# led_cube.net
KiCad netlist of a schematic drawn in EAGLE
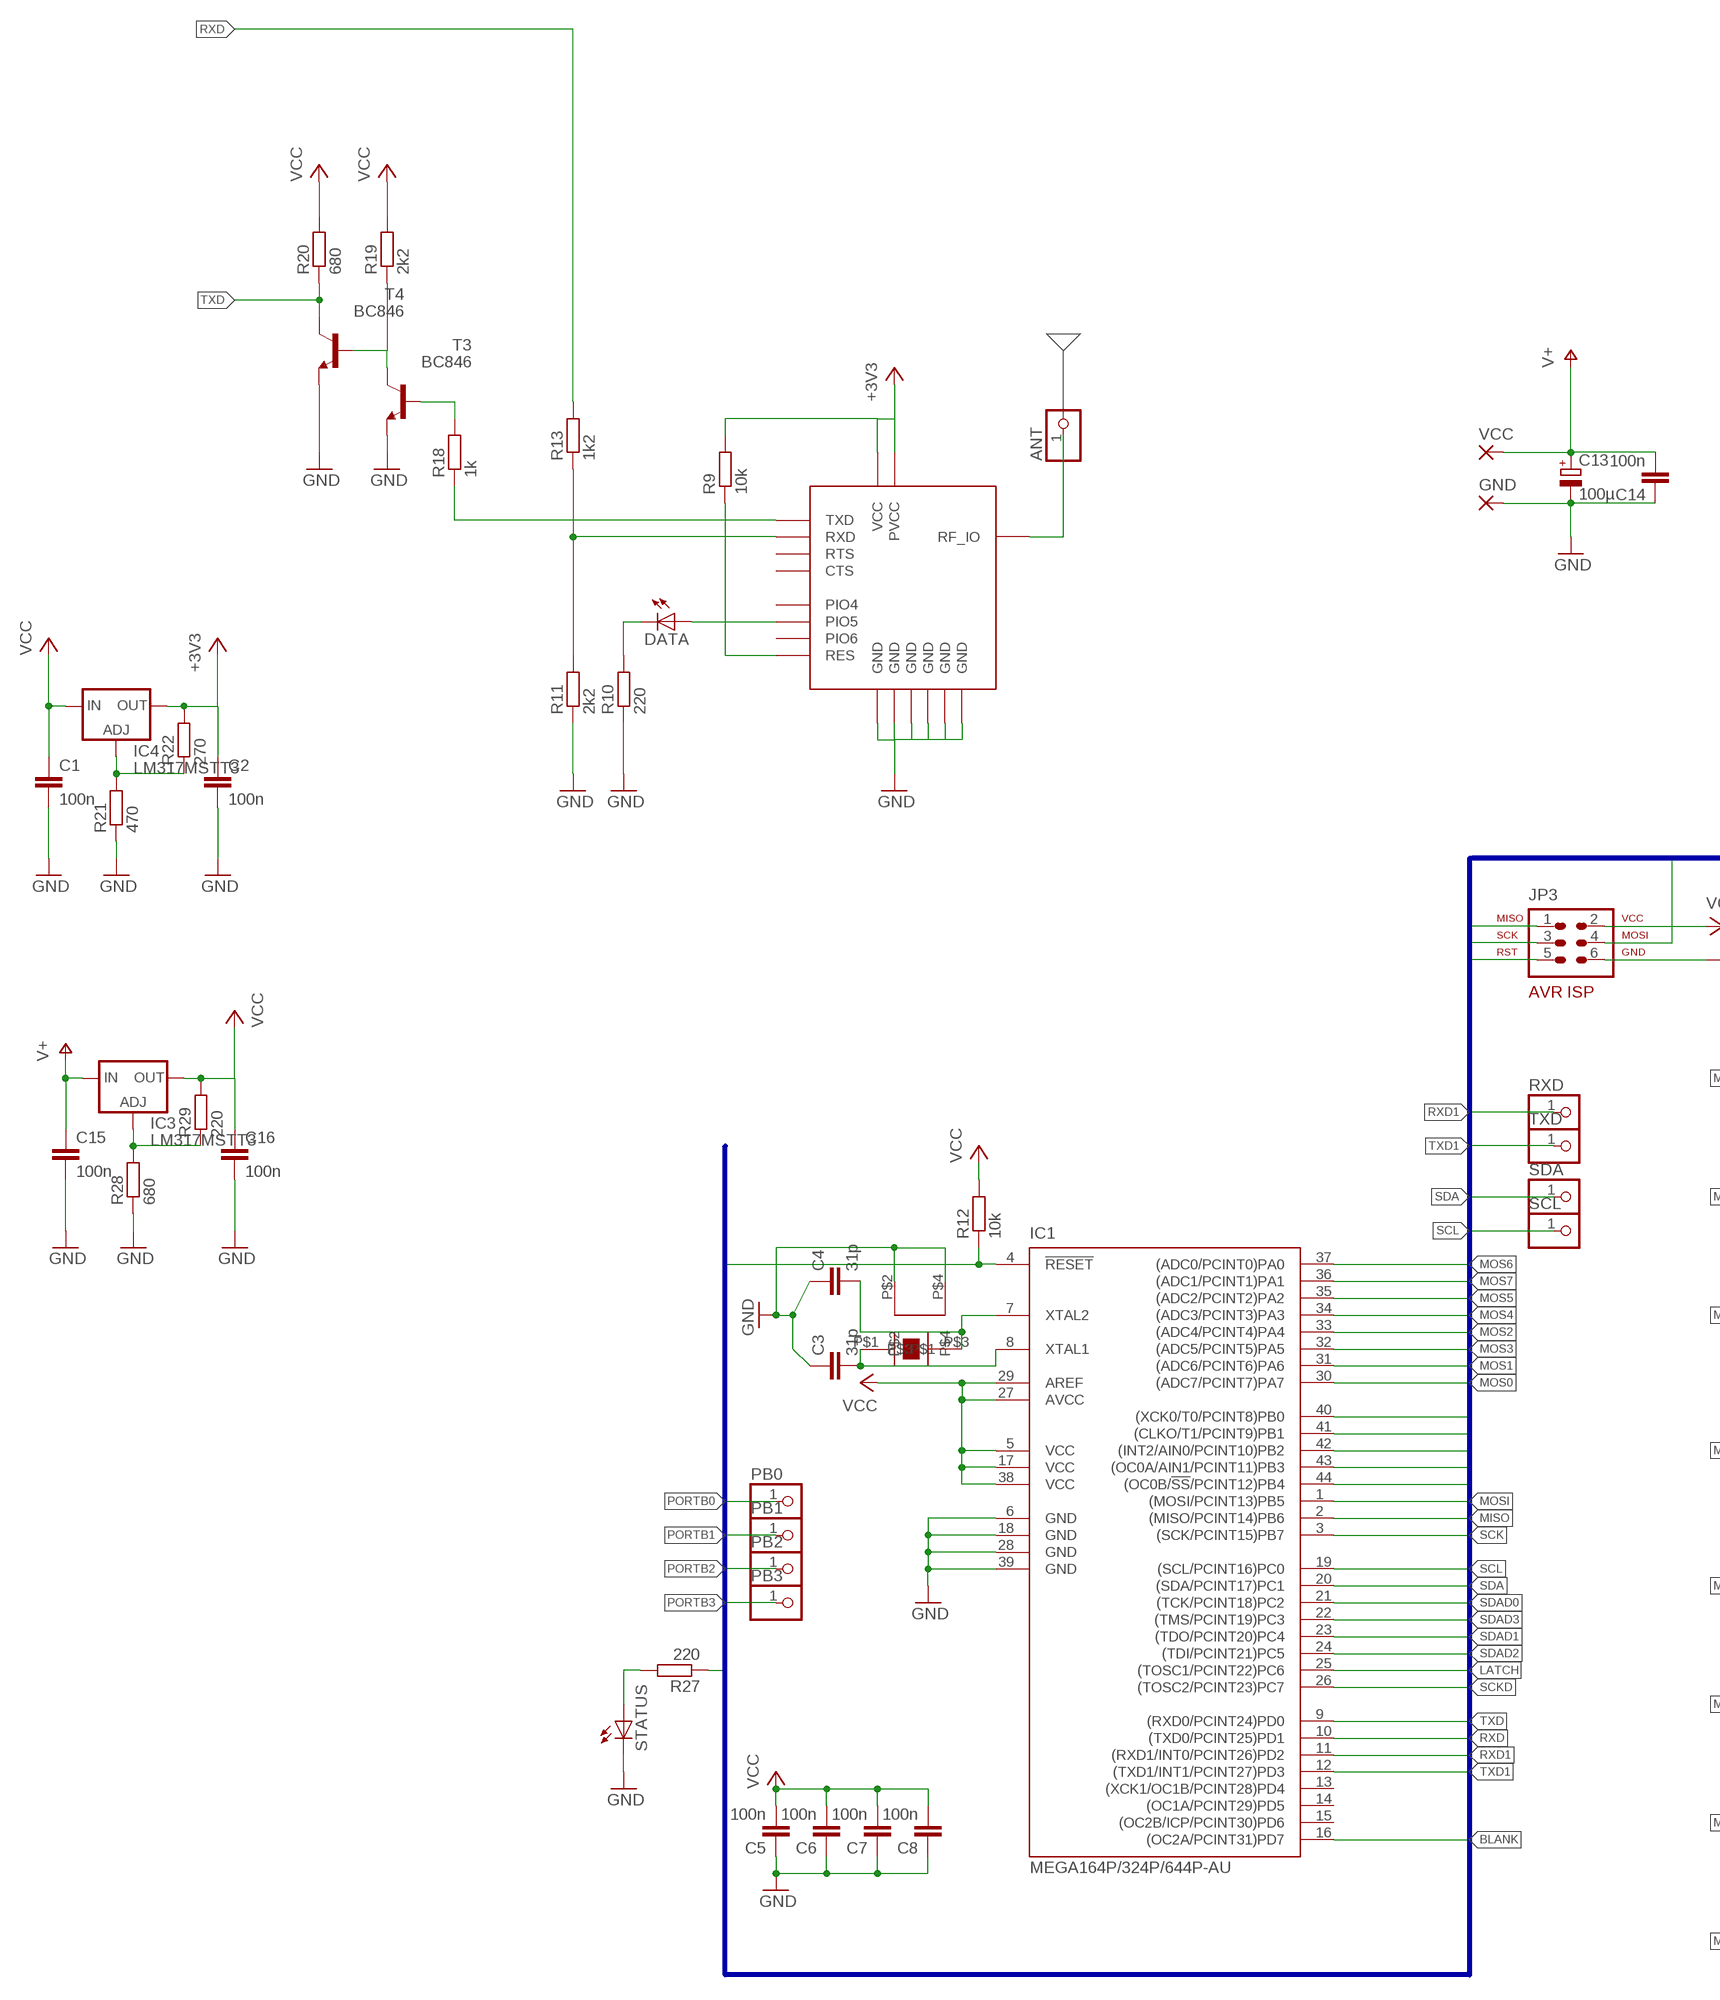
[diagram p0: schematic, sheet 1, part 1 of 2]
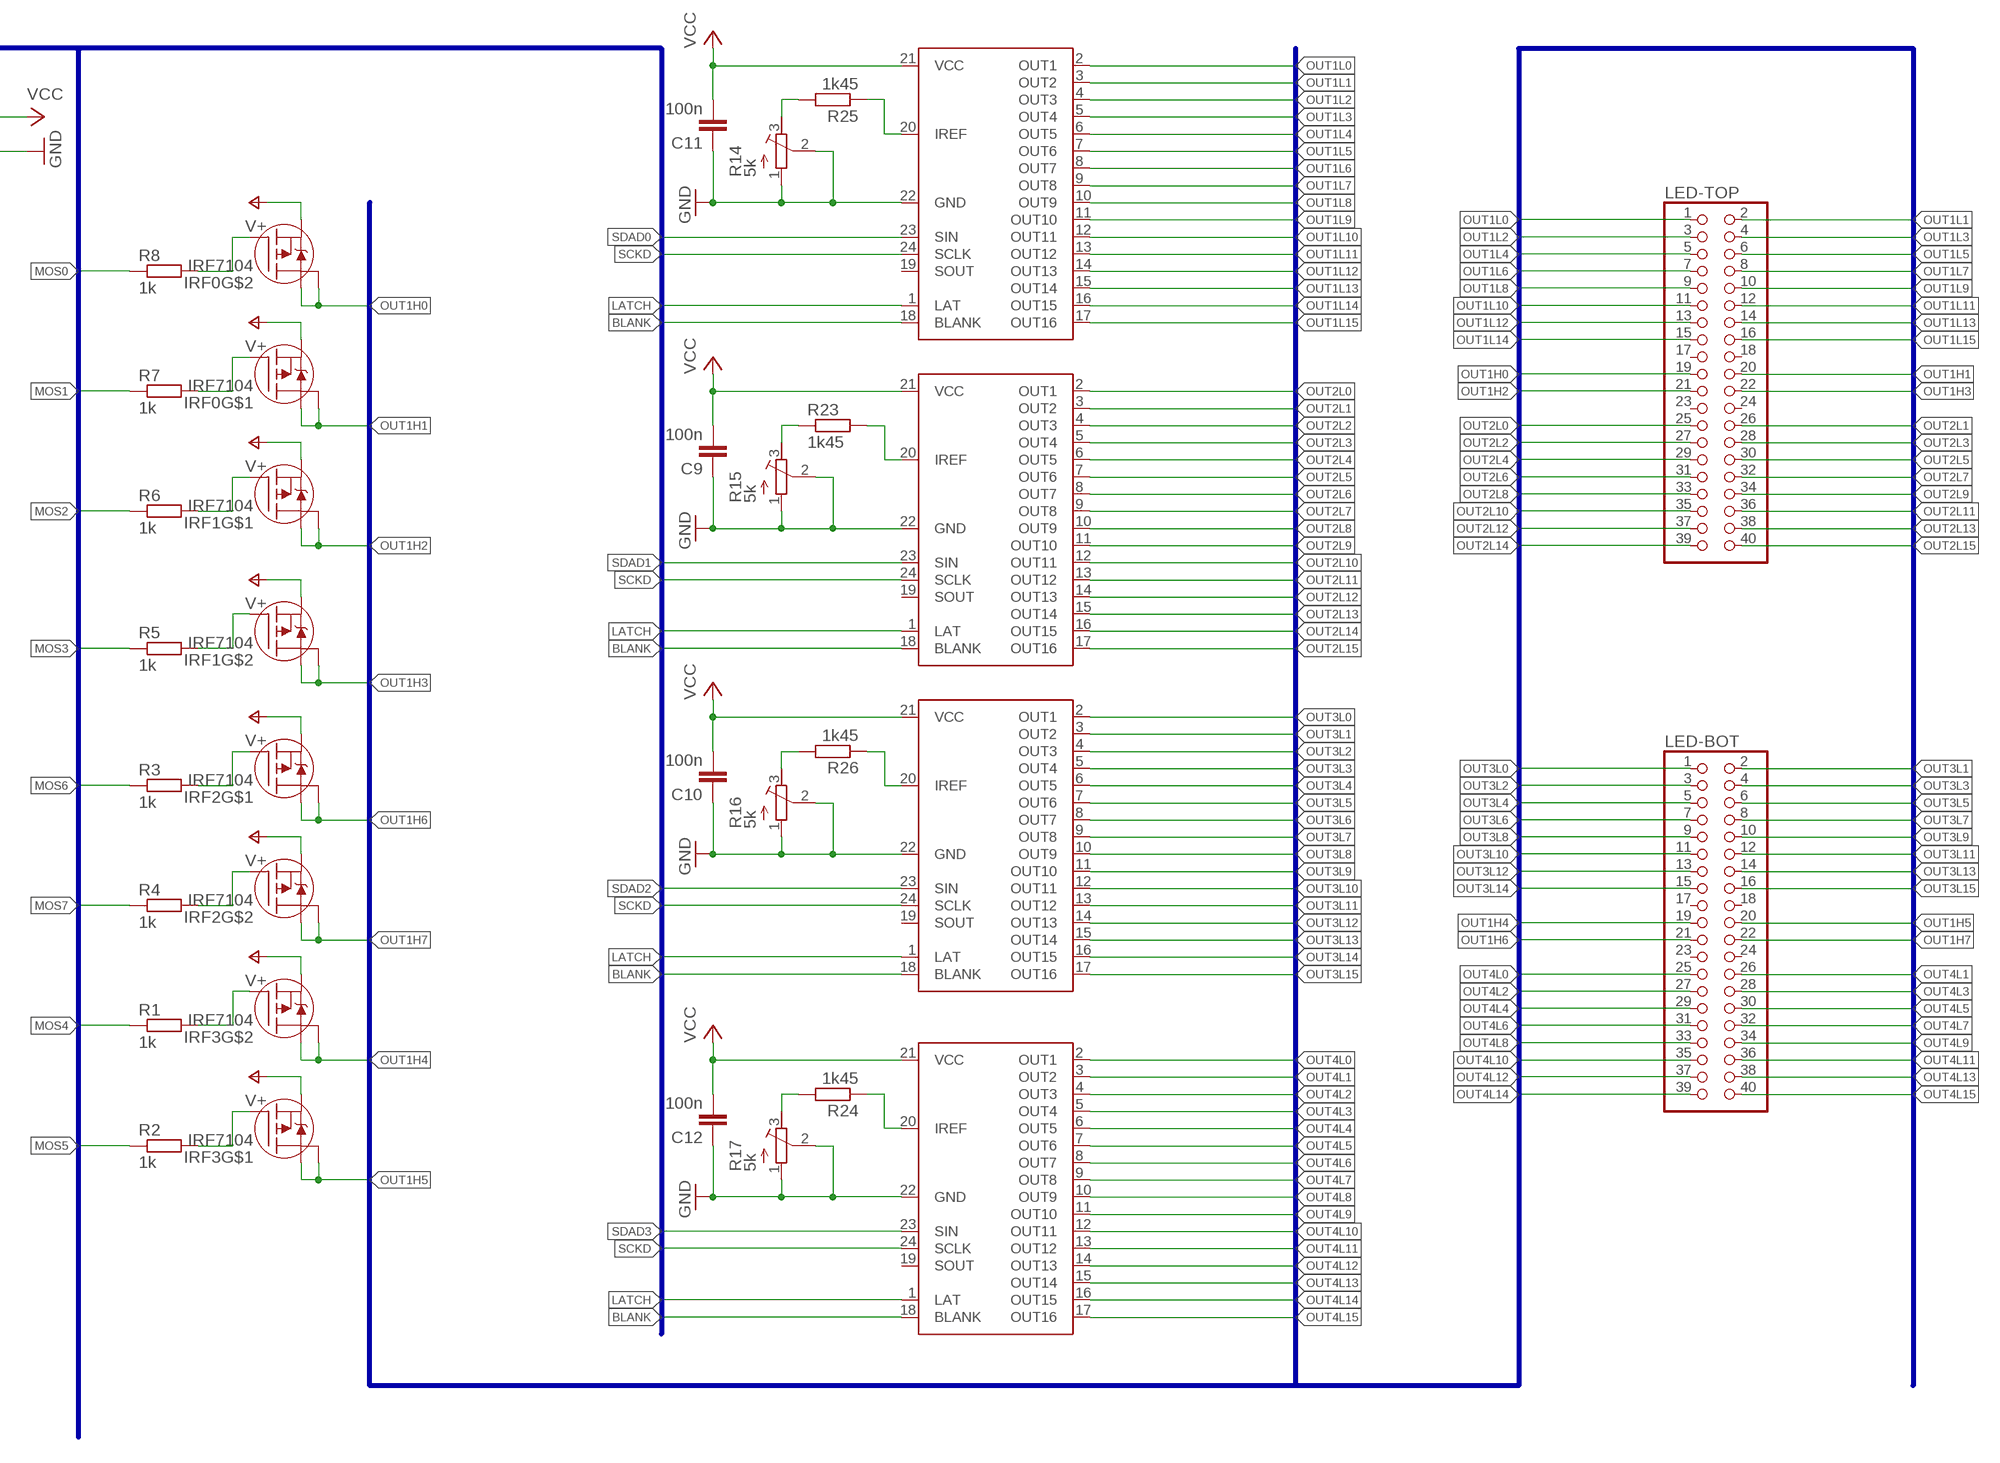
[diagram p1: schematic, sheet 1, part 2 of 2]

(export (version "E")
  (design (tool "Eeschema 10.0.6"))
  (components
    (comp (ref "ANT")
      (value "PINHD-1X1")
      (footprint "eagle-import:1X01")
      (libsource (lib "eagle-import") (part "PINHD-1X1"))
    )
    (comp (ref "C1")
      (value "100n")
      (footprint "eagle-import:C0805")
      (libsource (lib "eagle-import") (part "C-EUC0805"))
    )
    (comp (ref "C2")
      (value "100n")
      (footprint "eagle-import:C0805")
      (libsource (lib "eagle-import") (part "C-EUC0805"))
    )
    (comp (ref "C3")
      (value "31p")
      (footprint "eagle-import:C0805")
      (libsource (lib "eagle-import") (part "C-EUC0805"))
    )
    (comp (ref "C4")
      (value "31p")
      (footprint "eagle-import:C0805")
      (libsource (lib "eagle-import") (part "C-EUC0805"))
    )
    (comp (ref "C5")
      (value "100n")
      (footprint "eagle-import:C0805")
      (libsource (lib "eagle-import") (part "C-EUC0805"))
    )
    (comp (ref "C6")
      (value "100n")
      (footprint "eagle-import:C0805")
      (libsource (lib "eagle-import") (part "C-EUC0805"))
    )
    (comp (ref "C7")
      (value "100n")
      (footprint "eagle-import:C0805")
      (libsource (lib "eagle-import") (part "C-EUC0805"))
    )
    (comp (ref "C8")
      (value "100n")
      (footprint "eagle-import:C0805")
      (libsource (lib "eagle-import") (part "C-EUC0805"))
    )
    (comp (ref "C9")
      (value "100n")
      (footprint "eagle-import:C0805")
      (libsource (lib "eagle-import") (part "C-EUC0805"))
    )
    (comp (ref "C10")
      (value "100n")
      (footprint "eagle-import:C0805")
      (libsource (lib "eagle-import") (part "C-EUC0805"))
    )
    (comp (ref "C11")
      (value "100n")
      (footprint "eagle-import:C0805")
      (libsource (lib "eagle-import") (part "C-EUC0805"))
    )
    (comp (ref "C12")
      (value "100n")
      (footprint "eagle-import:C0805")
      (libsource (lib "eagle-import") (part "C-EUC0805"))
    )
    (comp (ref "C13")
      (value "100µ")
      (footprint "eagle-import:PANASONIC_D")
      (libsource (lib "eagle-import") (part "CPOL-EUD"))
    )
    (comp (ref "C14")
      (value "100n")
      (footprint "eagle-import:C0805")
      (libsource (lib "eagle-import") (part "C-EUC0805"))
    )
    (comp (ref "C15")
      (value "100n")
      (footprint "eagle-import:C0805")
      (libsource (lib "eagle-import") (part "C-EUC0805"))
    )
    (comp (ref "C16")
      (value "100n")
      (footprint "eagle-import:C0805")
      (libsource (lib "eagle-import") (part "C-EUC0805"))
    )
    (comp (ref "DATA")
      (value "LEDCHIPLED_1206")
      (footprint "eagle-import:CHIPLED_1206")
      (libsource (lib "eagle-import") (part "LEDCHIPLED_1206"))
    )
    (comp (ref "GND")
      (value "2,54/1,0")
      (footprint "eagle-import:2,54_1,0")
      (libsource (lib "eagle-import") (part "2,54/1,0"))
    )
    (comp (ref "IC1")
      (value "MEGA164P/324P/644P-AU")
      (footprint "eagle-import:TQFP44")
      (libsource (lib "eagle-import") (part "MEGA164P/324P/644P-AU"))
    )
    (comp (ref "IC2")
      (value "BTM_SER")
      (footprint "eagle-import:BTM_222")
      (libsource (lib "eagle-import") (part "BTM_SER"))
    )
    (comp (ref "IC3")
      (value "LM317MSTT3")
      (footprint "eagle-import:SOT223")
      (libsource (lib "eagle-import") (part "LM317?MSTT3"))
    )
    (comp (ref "IC4")
      (value "LM317MSTT3")
      (footprint "eagle-import:SOT223")
      (libsource (lib "eagle-import") (part "LM317?MSTT3"))
    )
    (comp (ref "IRF0")
      (value "IRF7104")
      (footprint "eagle-import:SO8-2")
      (libsource (lib "eagle-import") (part "IRF7104"))
    )
    (comp (ref "IRF1")
      (value "IRF7104")
      (footprint "eagle-import:SO8-2")
      (libsource (lib "eagle-import") (part "IRF7104"))
    )
    (comp (ref "IRF2")
      (value "IRF7104")
      (footprint "eagle-import:SO8-2")
      (libsource (lib "eagle-import") (part "IRF7104"))
    )
    (comp (ref "IRF3")
      (value "IRF7104")
      (footprint "eagle-import:SO8-2")
      (libsource (lib "eagle-import") (part "IRF7104"))
    )
    (comp (ref "JP3")
      (value "AVR-ISP-6VERT")
      (footprint "eagle-import:AVR-ISP-6")
      (libsource (lib "eagle-import") (part "AVR-ISP-6VERT"))
    )
    (comp (ref "LED-BOT")
      (value "PINHD-2X20")
      (footprint "eagle-import:2X20")
      (libsource (lib "eagle-import") (part "PINHD-2X20"))
    )
    (comp (ref "LED-TOP")
      (value "PINHD-2X20")
      (footprint "eagle-import:2X20")
      (libsource (lib "eagle-import") (part "PINHD-2X20"))
    )
    (comp (ref "PB0")
      (value "PINHD-1X1")
      (footprint "eagle-import:1X01")
      (libsource (lib "eagle-import") (part "PINHD-1X1"))
    )
    (comp (ref "PB1")
      (value "PINHD-1X1")
      (footprint "eagle-import:1X01")
      (libsource (lib "eagle-import") (part "PINHD-1X1"))
    )
    (comp (ref "PB2")
      (value "PINHD-1X1")
      (footprint "eagle-import:1X01")
      (libsource (lib "eagle-import") (part "PINHD-1X1"))
    )
    (comp (ref "PB3")
      (value "PINHD-1X1")
      (footprint "eagle-import:1X01")
      (libsource (lib "eagle-import") (part "PINHD-1X1"))
    )
    (comp (ref "R1")
      (value "1k")
      (footprint "eagle-import:R0805")
      (libsource (lib "eagle-import") (part "R-EU_R0805"))
    )
    (comp (ref "R2")
      (value "1k")
      (footprint "eagle-import:R0805")
      (libsource (lib "eagle-import") (part "R-EU_R0805"))
    )
    (comp (ref "R3")
      (value "1k")
      (footprint "eagle-import:R0805")
      (libsource (lib "eagle-import") (part "R-EU_R0805"))
    )
    (comp (ref "R4")
      (value "1k")
      (footprint "eagle-import:R0805")
      (libsource (lib "eagle-import") (part "R-EU_R0805"))
    )
    (comp (ref "R5")
      (value "1k")
      (footprint "eagle-import:R0805")
      (libsource (lib "eagle-import") (part "R-EU_R0805"))
    )
    (comp (ref "R6")
      (value "1k")
      (footprint "eagle-import:R0805")
      (libsource (lib "eagle-import") (part "R-EU_R0805"))
    )
    (comp (ref "R7")
      (value "1k")
      (footprint "eagle-import:R0805")
      (libsource (lib "eagle-import") (part "R-EU_R0805"))
    )
    (comp (ref "R8")
      (value "1k")
      (footprint "eagle-import:R0805")
      (libsource (lib "eagle-import") (part "R-EU_R0805"))
    )
    (comp (ref "R9")
      (value "10k")
      (footprint "eagle-import:R0805")
      (libsource (lib "eagle-import") (part "R-EU_R0805"))
    )
    (comp (ref "R10")
      (value "220")
      (footprint "eagle-import:R0805")
      (libsource (lib "eagle-import") (part "R-EU_R0805"))
    )
    (comp (ref "R11")
      (value "2k2")
      (footprint "eagle-import:R0805")
      (libsource (lib "eagle-import") (part "R-EU_R0805"))
    )
    (comp (ref "R12")
      (value "10k")
      (footprint "eagle-import:R0805")
      (libsource (lib "eagle-import") (part "R-EU_R0805"))
    )
    (comp (ref "R13")
      (value "1k2")
      (footprint "eagle-import:R0805")
      (libsource (lib "eagle-import") (part "R-EU_R0805"))
    )
    (comp (ref "R14")
      (value "5k")
      (footprint "eagle-import:RTRIM3202")
      (libsource (lib "eagle-import") (part "R-TRIMM3202"))
    )
    (comp (ref "R15")
      (value "5k")
      (footprint "eagle-import:RTRIM3202")
      (libsource (lib "eagle-import") (part "R-TRIMM3202"))
    )
    (comp (ref "R16")
      (value "5k")
      (footprint "eagle-import:RTRIM3202")
      (libsource (lib "eagle-import") (part "R-TRIMM3202"))
    )
    (comp (ref "R17")
      (value "5k")
      (footprint "eagle-import:RTRIM3202")
      (libsource (lib "eagle-import") (part "R-TRIMM3202"))
    )
    (comp (ref "R18")
      (value "1k")
      (footprint "eagle-import:R0805")
      (libsource (lib "eagle-import") (part "R-EU_R0805"))
    )
    (comp (ref "R19")
      (value "2k2")
      (footprint "eagle-import:R0805")
      (libsource (lib "eagle-import") (part "R-EU_R0805"))
    )
    (comp (ref "R20")
      (value "680")
      (footprint "eagle-import:R0805")
      (libsource (lib "eagle-import") (part "R-EU_R0805"))
    )
    (comp (ref "R21")
      (value "470")
      (footprint "eagle-import:R0805")
      (libsource (lib "eagle-import") (part "R-EU_R0805"))
    )
    (comp (ref "R22")
      (value "270")
      (footprint "eagle-import:R0805")
      (libsource (lib "eagle-import") (part "R-EU_R0805"))
    )
    (comp (ref "R23")
      (value "1k45")
      (footprint "eagle-import:R0805")
      (libsource (lib "eagle-import") (part "R-EU_R0805"))
    )
    (comp (ref "R24")
      (value "1k45")
      (footprint "eagle-import:R0805")
      (libsource (lib "eagle-import") (part "R-EU_R0805"))
    )
    (comp (ref "R25")
      (value "1k45")
      (footprint "eagle-import:R0805")
      (libsource (lib "eagle-import") (part "R-EU_R0805"))
    )
    (comp (ref "R26")
      (value "1k45")
      (footprint "eagle-import:R0805")
      (libsource (lib "eagle-import") (part "R-EU_R0805"))
    )
    (comp (ref "R27")
      (value "220")
      (footprint "eagle-import:R0805")
      (libsource (lib "eagle-import") (part "R-EU_R0805"))
    )
    (comp (ref "R28")
      (value "680")
      (footprint "eagle-import:R0805")
      (libsource (lib "eagle-import") (part "R-EU_R0805"))
    )
    (comp (ref "R29")
      (value "220")
      (footprint "eagle-import:R0805")
      (libsource (lib "eagle-import") (part "R-EU_R0805"))
    )
    (comp (ref "RXD")
      (value "PINHD-1X1")
      (footprint "eagle-import:1X01")
      (libsource (lib "eagle-import") (part "PINHD-1X1"))
    )
    (comp (ref "SCL")
      (value "PINHD-1X1")
      (footprint "eagle-import:1X01")
      (libsource (lib "eagle-import") (part "PINHD-1X1"))
    )
    (comp (ref "SDA")
      (value "PINHD-1X1")
      (footprint "eagle-import:1X01")
      (libsource (lib "eagle-import") (part "PINHD-1X1"))
    )
    (comp (ref "STATUS")
      (value "LEDCHIPLED_1206")
      (footprint "eagle-import:CHIPLED_1206")
      (libsource (lib "eagle-import") (part "LEDCHIPLED_1206"))
    )
    (comp (ref "T3")
      (value "BC846")
      (footprint "eagle-import:SOT23")
      (libsource (lib "eagle-import") (part "BC846"))
    )
    (comp (ref "T4")
      (value "BC846")
      (footprint "eagle-import:SOT23")
      (libsource (lib "eagle-import") (part "BC846"))
    )
    (comp (ref "TLC0")
      (value "TLC5929RGE")
      (footprint "eagle-import:HVQFN24")
      (libsource (lib "eagle-import") (part "TLC5929RGE"))
    )
    (comp (ref "TLC1")
      (value "TLC5929RGE")
      (footprint "eagle-import:HVQFN24")
      (libsource (lib "eagle-import") (part "TLC5929RGE"))
    )
    (comp (ref "TLC2")
      (value "TLC5929RGE")
      (footprint "eagle-import:HVQFN24")
      (libsource (lib "eagle-import") (part "TLC5929RGE"))
    )
    (comp (ref "TLC3")
      (value "TLC5929RGE")
      (footprint "eagle-import:HVQFN24")
      (libsource (lib "eagle-import") (part "TLC5929RGE"))
    )
    (comp (ref "TXD")
      (value "PINHD-1X1")
      (footprint "eagle-import:1X01")
      (libsource (lib "eagle-import") (part "PINHD-1X1"))
    )
    (comp (ref "U$9")
      (value "ABMM2")
      (footprint "eagle-import:ABMM2")
      (libsource (lib "eagle-import") (part "ABMM2"))
    )
    (comp (ref "VCC")
      (value "2,54/1,0")
      (footprint "eagle-import:2,54_1,0")
      (libsource (lib "eagle-import") (part "2,54/1,0"))
    )
  )
  (nets
    (net (code "1") (name "+3V3") (class "Default")
      (node (ref "C2") (pin "1") (pinfunction "1_1") (pintype "passive"))
      (node (ref "IC2") (pin "P$17") (pinfunction "VCC_P$17") (pintype "bidirectional"))
      (node (ref "IC2") (pin "P$2") (pinfunction "PVCC_P$2") (pintype "bidirectional"))
      (node (ref "IC4") (pin "4") (pinfunction "OUT_4") (pintype "passive"))
      (node (ref "R22") (pin "2") (pinfunction "2_2") (pintype "passive"))
      (node (ref "R9") (pin "2") (pinfunction "2_2") (pintype "passive"))
    )
    (net (code "2") (name "/PORTB4") (class "Default")
      (node (ref "IC1") (pin "44") (pinfunction "(OC0B/~{SS}/PCINT12)PB4_44") (pintype "bidirectional"))
      (node (ref "R27") (pin "1") (pinfunction "1_1") (pintype "passive"))
    )
    (net (code "3") (name "/RST") (class "Default")
      (node (ref "IC1") (pin "4") (pinfunction "~{RESET}_4") (pintype "input"))
      (node (ref "JP3") (pin "5") (pinfunction "5_5") (pintype "passive"))
      (node (ref "R12") (pin "1") (pinfunction "1_1") (pintype "passive"))
    )
    (net (code "4") (name "BLANK") (class "Default")
      (node (ref "IC1") (pin "16") (pinfunction "(OC2A/PCINT31)PD7_16") (pintype "bidirectional"))
      (node (ref "TLC0") (pin "18") (pinfunction "BLANK_18") (pintype "bidirectional"))
      (node (ref "TLC1") (pin "18") (pinfunction "BLANK_18") (pintype "bidirectional"))
      (node (ref "TLC2") (pin "18") (pinfunction "BLANK_18") (pintype "bidirectional"))
      (node (ref "TLC3") (pin "18") (pinfunction "BLANK_18") (pintype "bidirectional"))
    )
    (net (code "5") (name "GND") (class "Default")
      (node (ref "C1") (pin "2") (pinfunction "2_2") (pintype "passive"))
      (node (ref "C10") (pin "1") (pinfunction "1_1") (pintype "passive"))
      (node (ref "C11") (pin "1") (pinfunction "1_1") (pintype "passive"))
      (node (ref "C12") (pin "1") (pinfunction "1_1") (pintype "passive"))
      (node (ref "C13") (pin "-") (pinfunction "-_-") (pintype "passive"))
      (node (ref "C14") (pin "1") (pinfunction "1_1") (pintype "passive"))
      (node (ref "C15") (pin "2") (pinfunction "2_2") (pintype "passive"))
      (node (ref "C16") (pin "2") (pinfunction "2_2") (pintype "passive"))
      (node (ref "C2") (pin "2") (pinfunction "2_2") (pintype "passive"))
      (node (ref "C3") (pin "1") (pinfunction "1_1") (pintype "passive"))
      (node (ref "C4") (pin "1") (pinfunction "1_1") (pintype "passive"))
      (node (ref "C5") (pin "1") (pinfunction "1_1") (pintype "passive"))
      (node (ref "C6") (pin "1") (pinfunction "1_1") (pintype "passive"))
      (node (ref "C7") (pin "1") (pinfunction "1_1") (pintype "passive"))
      (node (ref "C8") (pin "1") (pinfunction "1_1") (pintype "passive"))
      (node (ref "C9") (pin "1") (pinfunction "1_1") (pintype "passive"))
      (node (ref "GND") (pin "1") (pinfunction "P_1") (pintype "passive"))
      (node (ref "IC1") (pin "18") (pinfunction "GND_18") (pintype "power_in"))
      (node (ref "IC1") (pin "28") (pinfunction "GND_28") (pintype "power_in"))
      (node (ref "IC1") (pin "39") (pinfunction "GND_39") (pintype "power_in"))
      (node (ref "IC1") (pin "6") (pinfunction "GND_6") (pintype "power_in"))
      (node (ref "IC2") (pin "P$1") (pinfunction "GND_P$1") (pintype "bidirectional"))
      (node (ref "IC2") (pin "P$10") (pinfunction "GND_P$10") (pintype "bidirectional"))
      (node (ref "IC2") (pin "P$18") (pinfunction "GND_P$18") (pintype "bidirectional"))
      (node (ref "IC2") (pin "P$19") (pinfunction "GND_P$19") (pintype "bidirectional"))
      (node (ref "IC2") (pin "P$29") (pinfunction "GND_P$29") (pintype "bidirectional"))
      (node (ref "IC2") (pin "P$38") (pinfunction "GND_P$38") (pintype "bidirectional"))
      (node (ref "JP3") (pin "6") (pinfunction "6_6") (pintype "passive"))
      (node (ref "R10") (pin "1") (pinfunction "1_1") (pintype "passive"))
      (node (ref "R11") (pin "1") (pinfunction "1_1") (pintype "passive"))
      (node (ref "R14") (pin "1") (pinfunction "A_1") (pintype "passive"))
      (node (ref "R14") (pin "2") (pinfunction "S_2") (pintype "passive"))
      (node (ref "R15") (pin "1") (pinfunction "A_1") (pintype "passive"))
      (node (ref "R15") (pin "2") (pinfunction "S_2") (pintype "passive"))
      (node (ref "R16") (pin "1") (pinfunction "A_1") (pintype "passive"))
      (node (ref "R16") (pin "2") (pinfunction "S_2") (pintype "passive"))
      (node (ref "R17") (pin "1") (pinfunction "A_1") (pintype "passive"))
      (node (ref "R17") (pin "2") (pinfunction "S_2") (pintype "passive"))
      (node (ref "R21") (pin "1") (pinfunction "1_1") (pintype "passive"))
      (node (ref "R28") (pin "1") (pinfunction "1_1") (pintype "passive"))
      (node (ref "STATUS") (pin "C") (pinfunction "C_C") (pintype "passive"))
      (node (ref "T3") (pin "2") (pinfunction "E_2") (pintype "passive"))
      (node (ref "T4") (pin "2") (pinfunction "E_2") (pintype "passive"))
      (node (ref "TLC0") (pin "22") (pinfunction "GND_22") (pintype "bidirectional"))
      (node (ref "TLC1") (pin "22") (pinfunction "GND_22") (pintype "bidirectional"))
      (node (ref "TLC2") (pin "22") (pinfunction "GND_22") (pintype "bidirectional"))
      (node (ref "TLC3") (pin "22") (pinfunction "GND_22") (pintype "bidirectional"))
      (node (ref "U$9") (pin "P$2") (pinfunction "P$2_P$2") (pintype "bidirectional"))
      (node (ref "U$9") (pin "P$4") (pinfunction "P$4_P$4") (pintype "bidirectional"))
    )
    (net (code "6") (name "LATCH") (class "Default")
      (node (ref "IC1") (pin "25") (pinfunction "(TOSC1/PCINT22)PC6_25") (pintype "bidirectional"))
      (node (ref "TLC0") (pin "1") (pinfunction "LAT_1") (pintype "bidirectional"))
      (node (ref "TLC1") (pin "1") (pinfunction "LAT_1") (pintype "bidirectional"))
      (node (ref "TLC2") (pin "1") (pinfunction "LAT_1") (pintype "bidirectional"))
      (node (ref "TLC3") (pin "1") (pinfunction "LAT_1") (pintype "bidirectional"))
    )
    (net (code "7") (name "MISO") (class "Default")
      (node (ref "IC1") (pin "2") (pinfunction "(MISO/PCINT14)PB6_2") (pintype "bidirectional"))
      (node (ref "JP3") (pin "1") (pinfunction "1_1") (pintype "passive"))
    )
    (net (code "8") (name "MOS0") (class "Default")
      (node (ref "IC1") (pin "30") (pinfunction "(ADC7/PCINT7)PA7_30") (pintype "bidirectional"))
      (node (ref "R8") (pin "1") (pinfunction "1_1") (pintype "passive"))
    )
    (net (code "9") (name "MOS1") (class "Default")
      (node (ref "IC1") (pin "31") (pinfunction "(ADC6/PCINT6)PA6_31") (pintype "bidirectional"))
      (node (ref "R7") (pin "1") (pinfunction "1_1") (pintype "passive"))
    )
    (net (code "10") (name "MOS2") (class "Default")
      (node (ref "IC1") (pin "33") (pinfunction "(ADC4/PCINT4)PA4_33") (pintype "bidirectional"))
      (node (ref "R6") (pin "1") (pinfunction "1_1") (pintype "passive"))
    )
    (net (code "11") (name "MOS3") (class "Default")
      (node (ref "IC1") (pin "32") (pinfunction "(ADC5/PCINT5)PA5_32") (pintype "bidirectional"))
      (node (ref "R5") (pin "1") (pinfunction "1_1") (pintype "passive"))
    )
    (net (code "12") (name "MOS4") (class "Default")
      (node (ref "IC1") (pin "34") (pinfunction "(ADC3/PCINT3)PA3_34") (pintype "bidirectional"))
      (node (ref "R1") (pin "1") (pinfunction "1_1") (pintype "passive"))
    )
    (net (code "13") (name "MOS5") (class "Default")
      (node (ref "IC1") (pin "35") (pinfunction "(ADC2/PCINT2)PA2_35") (pintype "bidirectional"))
      (node (ref "R2") (pin "1") (pinfunction "1_1") (pintype "passive"))
    )
    (net (code "14") (name "MOS6") (class "Default")
      (node (ref "IC1") (pin "37") (pinfunction "(ADC0/PCINT0)PA0_37") (pintype "bidirectional"))
      (node (ref "R3") (pin "1") (pinfunction "1_1") (pintype "passive"))
    )
    (net (code "15") (name "MOS7") (class "Default")
      (node (ref "IC1") (pin "36") (pinfunction "(ADC1/PCINT1)PA1_36") (pintype "bidirectional"))
      (node (ref "R4") (pin "1") (pinfunction "1_1") (pintype "passive"))
    )
    (net (code "16") (name "MOSI") (class "Default")
      (node (ref "IC1") (pin "1") (pinfunction "(MOSI/PCINT13)PB5_1") (pintype "bidirectional"))
      (node (ref "JP3") (pin "4") (pinfunction "4_4") (pintype "passive"))
    )
    (net (code "17") (name "Net-(DATA-PadC)") (class "Default")
      (node (ref "DATA") (pin "C") (pinfunction "C_C") (pintype "passive"))
      (node (ref "R10") (pin "2") (pinfunction "2_2") (pintype "passive"))
    )
    (net (code "18") (name "Net-(IC1-XTAL1)") (class "Default")
      (node (ref "C3") (pin "2") (pinfunction "2_2") (pintype "passive"))
      (node (ref "IC1") (pin "8") (pinfunction "XTAL1_8") (pintype "input"))
      (node (ref "U$9") (pin "P$1") (pinfunction "P$1_P$1") (pintype "bidirectional"))
    )
    (net (code "19") (name "Net-(IC1-XTAL2)") (class "Default")
      (node (ref "C4") (pin "2") (pinfunction "2_2") (pintype "passive"))
      (node (ref "IC1") (pin "7") (pinfunction "XTAL2_7") (pintype "output"))
      (node (ref "U$9") (pin "P$3") (pinfunction "P$3_P$3") (pintype "bidirectional"))
    )
    (net (code "20") (name "Net-(IC2-PIO5)") (class "Default")
      (node (ref "DATA") (pin "A") (pinfunction "A_A") (pintype "passive"))
      (node (ref "IC2") (pin "P$11") (pinfunction "PIO5_P$11") (pintype "bidirectional"))
    )
    (net (code "21") (name "Net-(IC2-RES)") (class "Default")
      (node (ref "IC2") (pin "P$16") (pinfunction "RES_P$16") (pintype "bidirectional"))
      (node (ref "R9") (pin "1") (pinfunction "1_1") (pintype "passive"))
    )
    (net (code "22") (name "Net-(IC2-RF_IO)") (class "Default")
      (node (ref "ANT") (pin "1") (pinfunction "1_1") (pintype "passive"))
      (node (ref "IC2") (pin "P$37") (pinfunction "RF_IO_P$37") (pintype "bidirectional"))
    )
    (net (code "23") (name "Net-(IC2-RXD)") (class "Default")
      (node (ref "IC2") (pin "P$26") (pinfunction "RXD_P$26") (pintype "bidirectional"))
      (node (ref "R11") (pin "2") (pinfunction "2_2") (pintype "passive"))
      (node (ref "R13") (pin "1") (pinfunction "1_1") (pintype "passive"))
    )
    (net (code "24") (name "Net-(IC2-TXD)") (class "Default")
      (node (ref "IC2") (pin "P$27") (pinfunction "TXD_P$27") (pintype "bidirectional"))
      (node (ref "R18") (pin "1") (pinfunction "1_1") (pintype "passive"))
    )
    (net (code "25") (name "Net-(IC3-ADJ)") (class "Default")
      (node (ref "IC3") (pin "1") (pinfunction "ADJ_1") (pintype "input"))
      (node (ref "R28") (pin "2") (pinfunction "2_2") (pintype "passive"))
      (node (ref "R29") (pin "1") (pinfunction "1_1") (pintype "passive"))
    )
    (net (code "26") (name "Net-(IC4-ADJ)") (class "Default")
      (node (ref "IC4") (pin "1") (pinfunction "ADJ_1") (pintype "input"))
      (node (ref "R21") (pin "2") (pinfunction "2_2") (pintype "passive"))
      (node (ref "R22") (pin "1") (pinfunction "1_1") (pintype "passive"))
    )
    (net (code "27") (name "Net-(IRF0A-G)") (class "Default")
      (node (ref "IRF0") (pin "2") (pinfunction "G_2") (pintype "bidirectional"))
      (node (ref "R7") (pin "2") (pinfunction "2_2") (pintype "passive"))
    )
    (net (code "28") (name "Net-(IRF0B-G)") (class "Default")
      (node (ref "IRF0") (pin "4") (pinfunction "G_4") (pintype "bidirectional"))
      (node (ref "R8") (pin "2") (pinfunction "2_2") (pintype "passive"))
    )
    (net (code "29") (name "Net-(IRF1A-G)") (class "Default")
      (node (ref "IRF1") (pin "2") (pinfunction "G_2") (pintype "bidirectional"))
      (node (ref "R6") (pin "2") (pinfunction "2_2") (pintype "passive"))
    )
    (net (code "30") (name "Net-(IRF1B-G)") (class "Default")
      (node (ref "IRF1") (pin "4") (pinfunction "G_4") (pintype "bidirectional"))
      (node (ref "R5") (pin "2") (pinfunction "2_2") (pintype "passive"))
    )
    (net (code "31") (name "Net-(IRF2A-G)") (class "Default")
      (node (ref "IRF2") (pin "2") (pinfunction "G_2") (pintype "bidirectional"))
      (node (ref "R3") (pin "2") (pinfunction "2_2") (pintype "passive"))
    )
    (net (code "32") (name "Net-(IRF2B-G)") (class "Default")
      (node (ref "IRF2") (pin "4") (pinfunction "G_4") (pintype "bidirectional"))
      (node (ref "R4") (pin "2") (pinfunction "2_2") (pintype "passive"))
    )
    (net (code "33") (name "Net-(IRF3A-G)") (class "Default")
      (node (ref "IRF3") (pin "2") (pinfunction "G_2") (pintype "bidirectional"))
      (node (ref "R2") (pin "2") (pinfunction "2_2") (pintype "passive"))
    )
    (net (code "34") (name "Net-(IRF3B-G)") (class "Default")
      (node (ref "IRF3") (pin "4") (pinfunction "G_4") (pintype "bidirectional"))
      (node (ref "R1") (pin "2") (pinfunction "2_2") (pintype "passive"))
    )
    (net (code "35") (name "Net-(R14-E)") (class "Default")
      (node (ref "R14") (pin "3") (pinfunction "E_3") (pintype "passive"))
      (node (ref "R25") (pin "2") (pinfunction "2_2") (pintype "passive"))
    )
    (net (code "36") (name "Net-(R15-E)") (class "Default")
      (node (ref "R15") (pin "3") (pinfunction "E_3") (pintype "passive"))
      (node (ref "R23") (pin "1") (pinfunction "1_1") (pintype "passive"))
    )
    (net (code "37") (name "Net-(R16-E)") (class "Default")
      (node (ref "R16") (pin "3") (pinfunction "E_3") (pintype "passive"))
      (node (ref "R26") (pin "2") (pinfunction "2_2") (pintype "passive"))
    )
    (net (code "38") (name "Net-(R17-E)") (class "Default")
      (node (ref "R17") (pin "3") (pinfunction "E_3") (pintype "passive"))
      (node (ref "R24") (pin "2") (pinfunction "2_2") (pintype "passive"))
    )
    (net (code "39") (name "Net-(R27-Pad2)") (class "Default")
      (node (ref "R27") (pin "2") (pinfunction "2_2") (pintype "passive"))
      (node (ref "STATUS") (pin "A") (pinfunction "A_A") (pintype "passive"))
    )
    (net (code "40") (name "Net-(T3-B)") (class "Default")
      (node (ref "R18") (pin "2") (pinfunction "2_2") (pintype "passive"))
      (node (ref "T3") (pin "1") (pinfunction "B_1") (pintype "passive"))
    )
    (net (code "41") (name "Net-(T3-C)") (class "Default")
      (node (ref "R19") (pin "1") (pinfunction "1_1") (pintype "passive"))
      (node (ref "T3") (pin "3") (pinfunction "C_3") (pintype "passive"))
      (node (ref "T4") (pin "1") (pinfunction "B_1") (pintype "passive"))
    )
    (net (code "42") (name "Net-(TLC0-IREF)") (class "Default")
      (node (ref "R25") (pin "1") (pinfunction "1_1") (pintype "passive"))
      (node (ref "TLC0") (pin "20") (pinfunction "IREF_20") (pintype "bidirectional"))
    )
    (net (code "43") (name "Net-(TLC1-IREF)") (class "Default")
      (node (ref "R23") (pin "2") (pinfunction "2_2") (pintype "passive"))
      (node (ref "TLC1") (pin "20") (pinfunction "IREF_20") (pintype "bidirectional"))
    )
    (net (code "44") (name "Net-(TLC2-IREF)") (class "Default")
      (node (ref "R26") (pin "1") (pinfunction "1_1") (pintype "passive"))
      (node (ref "TLC2") (pin "20") (pinfunction "IREF_20") (pintype "bidirectional"))
    )
    (net (code "45") (name "Net-(TLC3-IREF)") (class "Default")
      (node (ref "R24") (pin "1") (pinfunction "1_1") (pintype "passive"))
      (node (ref "TLC3") (pin "20") (pinfunction "IREF_20") (pintype "bidirectional"))
    )
    (net (code "46") (name "OUT1H0") (class "Default")
      (node (ref "IRF0") (pin "5") (pinfunction "D_5") (pintype "bidirectional"))
      (node (ref "IRF0") (pin "6") (pinfunction "D_6") (pintype "bidirectional"))
      (node (ref "LED-TOP") (pin "19") (pinfunction "19_19") (pintype "passive"))
    )
    (net (code "47") (name "OUT1H1") (class "Default")
      (node (ref "IRF0") (pin "7") (pinfunction "D_7") (pintype "bidirectional"))
      (node (ref "IRF0") (pin "8") (pinfunction "D_8") (pintype "bidirectional"))
      (node (ref "LED-TOP") (pin "20") (pinfunction "20_20") (pintype "passive"))
    )
    (net (code "48") (name "OUT1H2") (class "Default")
      (node (ref "IRF1") (pin "7") (pinfunction "D_7") (pintype "bidirectional"))
      (node (ref "IRF1") (pin "8") (pinfunction "D_8") (pintype "bidirectional"))
      (node (ref "LED-TOP") (pin "21") (pinfunction "21_21") (pintype "passive"))
    )
    (net (code "49") (name "OUT1H3") (class "Default")
      (node (ref "IRF1") (pin "5") (pinfunction "D_5") (pintype "bidirectional"))
      (node (ref "IRF1") (pin "6") (pinfunction "D_6") (pintype "bidirectional"))
      (node (ref "LED-TOP") (pin "22") (pinfunction "22_22") (pintype "passive"))
    )
    (net (code "50") (name "OUT1H4") (class "Default")
      (node (ref "IRF3") (pin "5") (pinfunction "D_5") (pintype "bidirectional"))
      (node (ref "IRF3") (pin "6") (pinfunction "D_6") (pintype "bidirectional"))
      (node (ref "LED-BOT") (pin "19") (pinfunction "19_19") (pintype "passive"))
    )
    (net (code "51") (name "OUT1H5") (class "Default")
      (node (ref "IRF3") (pin "7") (pinfunction "D_7") (pintype "bidirectional"))
      (node (ref "IRF3") (pin "8") (pinfunction "D_8") (pintype "bidirectional"))
      (node (ref "LED-BOT") (pin "20") (pinfunction "20_20") (pintype "passive"))
    )
    (net (code "52") (name "OUT1H6") (class "Default")
      (node (ref "IRF2") (pin "7") (pinfunction "D_7") (pintype "bidirectional"))
      (node (ref "IRF2") (pin "8") (pinfunction "D_8") (pintype "bidirectional"))
      (node (ref "LED-BOT") (pin "21") (pinfunction "21_21") (pintype "passive"))
    )
    (net (code "53") (name "OUT1H7") (class "Default")
      (node (ref "IRF2") (pin "5") (pinfunction "D_5") (pintype "bidirectional"))
      (node (ref "IRF2") (pin "6") (pinfunction "D_6") (pintype "bidirectional"))
      (node (ref "LED-BOT") (pin "22") (pinfunction "22_22") (pintype "passive"))
    )
    (net (code "54") (name "OUT1L0") (class "Default")
      (node (ref "LED-TOP") (pin "1") (pinfunction "1_1") (pintype "passive"))
      (node (ref "TLC0") (pin "2") (pinfunction "OUT1_2") (pintype "bidirectional"))
    )
    (net (code "55") (name "OUT1L1") (class "Default")
      (node (ref "LED-TOP") (pin "2") (pinfunction "2_2") (pintype "passive"))
      (node (ref "TLC0") (pin "3") (pinfunction "OUT2_3") (pintype "bidirectional"))
    )
    (net (code "56") (name "OUT1L2") (class "Default")
      (node (ref "LED-TOP") (pin "3") (pinfunction "3_3") (pintype "passive"))
      (node (ref "TLC0") (pin "4") (pinfunction "OUT3_4") (pintype "bidirectional"))
    )
    (net (code "57") (name "OUT1L3") (class "Default")
      (node (ref "LED-TOP") (pin "4") (pinfunction "4_4") (pintype "passive"))
      (node (ref "TLC0") (pin "5") (pinfunction "OUT4_5") (pintype "bidirectional"))
    )
    (net (code "58") (name "OUT1L4") (class "Default")
      (node (ref "LED-TOP") (pin "5") (pinfunction "5_5") (pintype "passive"))
      (node (ref "TLC0") (pin "6") (pinfunction "OUT5_6") (pintype "bidirectional"))
    )
    (net (code "59") (name "OUT1L5") (class "Default")
      (node (ref "LED-TOP") (pin "6") (pinfunction "6_6") (pintype "passive"))
      (node (ref "TLC0") (pin "7") (pinfunction "OUT6_7") (pintype "bidirectional"))
    )
    (net (code "60") (name "OUT1L6") (class "Default")
      (node (ref "LED-TOP") (pin "7") (pinfunction "7_7") (pintype "passive"))
      (node (ref "TLC0") (pin "8") (pinfunction "OUT7_8") (pintype "bidirectional"))
    )
    (net (code "61") (name "OUT1L7") (class "Default")
      (node (ref "LED-TOP") (pin "8") (pinfunction "8_8") (pintype "passive"))
      (node (ref "TLC0") (pin "9") (pinfunction "OUT8_9") (pintype "bidirectional"))
    )
    (net (code "62") (name "OUT1L8") (class "Default")
      (node (ref "LED-TOP") (pin "9") (pinfunction "9_9") (pintype "passive"))
      (node (ref "TLC0") (pin "10") (pinfunction "OUT9_10") (pintype "bidirectional"))
    )
    (net (code "63") (name "OUT1L9") (class "Default")
      (node (ref "LED-TOP") (pin "10") (pinfunction "10_10") (pintype "passive"))
      (node (ref "TLC0") (pin "11") (pinfunction "OUT10_11") (pintype "bidirectional"))
    )
    (net (code "64") (name "OUT1L10") (class "Default")
      (node (ref "LED-TOP") (pin "11") (pinfunction "11_11") (pintype "passive"))
      (node (ref "TLC0") (pin "12") (pinfunction "OUT11_12") (pintype "bidirectional"))
    )
    (net (code "65") (name "OUT1L11") (class "Default")
      (node (ref "LED-TOP") (pin "12") (pinfunction "12_12") (pintype "passive"))
      (node (ref "TLC0") (pin "13") (pinfunction "OUT12_13") (pintype "bidirectional"))
    )
    (net (code "66") (name "OUT1L12") (class "Default")
      (node (ref "LED-TOP") (pin "13") (pinfunction "13_13") (pintype "passive"))
      (node (ref "TLC0") (pin "14") (pinfunction "OUT13_14") (pintype "bidirectional"))
    )
    (net (code "67") (name "OUT1L13") (class "Default")
      (node (ref "LED-TOP") (pin "14") (pinfunction "14_14") (pintype "passive"))
      (node (ref "TLC0") (pin "15") (pinfunction "OUT14_15") (pintype "bidirectional"))
    )
    (net (code "68") (name "OUT1L14") (class "Default")
      (node (ref "LED-TOP") (pin "15") (pinfunction "15_15") (pintype "passive"))
      (node (ref "TLC0") (pin "16") (pinfunction "OUT15_16") (pintype "bidirectional"))
    )
    (net (code "69") (name "OUT1L15") (class "Default")
      (node (ref "LED-TOP") (pin "16") (pinfunction "16_16") (pintype "passive"))
      (node (ref "TLC0") (pin "17") (pinfunction "OUT16_17") (pintype "bidirectional"))
    )
    (net (code "70") (name "OUT2L0") (class "Default")
      (node (ref "LED-TOP") (pin "25") (pinfunction "25_25") (pintype "passive"))
      (node (ref "TLC1") (pin "2") (pinfunction "OUT1_2") (pintype "bidirectional"))
    )
    (net (code "71") (name "OUT2L1") (class "Default")
      (node (ref "LED-TOP") (pin "26") (pinfunction "26_26") (pintype "passive"))
      (node (ref "TLC1") (pin "3") (pinfunction "OUT2_3") (pintype "bidirectional"))
    )
    (net (code "72") (name "OUT2L2") (class "Default")
      (node (ref "LED-TOP") (pin "27") (pinfunction "27_27") (pintype "passive"))
      (node (ref "TLC1") (pin "4") (pinfunction "OUT3_4") (pintype "bidirectional"))
    )
    (net (code "73") (name "OUT2L3") (class "Default")
      (node (ref "LED-TOP") (pin "28") (pinfunction "28_28") (pintype "passive"))
      (node (ref "TLC1") (pin "5") (pinfunction "OUT4_5") (pintype "bidirectional"))
    )
    (net (code "74") (name "OUT2L4") (class "Default")
      (node (ref "LED-TOP") (pin "29") (pinfunction "29_29") (pintype "passive"))
      (node (ref "TLC1") (pin "6") (pinfunction "OUT5_6") (pintype "bidirectional"))
    )
    (net (code "75") (name "OUT2L5") (class "Default")
      (node (ref "LED-TOP") (pin "30") (pinfunction "30_30") (pintype "passive"))
      (node (ref "TLC1") (pin "7") (pinfunction "OUT6_7") (pintype "bidirectional"))
    )
    (net (code "76") (name "OUT2L6") (class "Default")
      (node (ref "LED-TOP") (pin "31") (pinfunction "31_31") (pintype "passive"))
      (node (ref "TLC1") (pin "8") (pinfunction "OUT7_8") (pintype "bidirectional"))
    )
    (net (code "77") (name "OUT2L7") (class "Default")
      (node (ref "LED-TOP") (pin "32") (pinfunction "32_32") (pintype "passive"))
      (node (ref "TLC1") (pin "9") (pinfunction "OUT8_9") (pintype "bidirectional"))
    )
    (net (code "78") (name "OUT2L8") (class "Default")
      (node (ref "LED-TOP") (pin "33") (pinfunction "33_33") (pintype "passive"))
      (node (ref "TLC1") (pin "10") (pinfunction "OUT9_10") (pintype "bidirectional"))
    )
    (net (code "79") (name "OUT2L9") (class "Default")
      (node (ref "LED-TOP") (pin "34") (pinfunction "34_34") (pintype "passive"))
      (node (ref "TLC1") (pin "11") (pinfunction "OUT10_11") (pintype "bidirectional"))
    )
    (net (code "80") (name "OUT2L10") (class "Default")
      (node (ref "LED-TOP") (pin "35") (pinfunction "35_35") (pintype "passive"))
      (node (ref "TLC1") (pin "12") (pinfunction "OUT11_12") (pintype "bidirectional"))
    )
    (net (code "81") (name "OUT2L11") (class "Default")
      (node (ref "LED-TOP") (pin "36") (pinfunction "36_36") (pintype "passive"))
      (node (ref "TLC1") (pin "13") (pinfunction "OUT12_13") (pintype "bidirectional"))
    )
    (net (code "82") (name "OUT2L12") (class "Default")
      (node (ref "LED-TOP") (pin "37") (pinfunction "37_37") (pintype "passive"))
      (node (ref "TLC1") (pin "14") (pinfunction "OUT13_14") (pintype "bidirectional"))
    )
    (net (code "83") (name "OUT2L13") (class "Default")
      (node (ref "LED-TOP") (pin "38") (pinfunction "38_38") (pintype "passive"))
      (node (ref "TLC1") (pin "15") (pinfunction "OUT14_15") (pintype "bidirectional"))
    )
    (net (code "84") (name "OUT2L14") (class "Default")
      (node (ref "LED-TOP") (pin "39") (pinfunction "39_39") (pintype "passive"))
      (node (ref "TLC1") (pin "16") (pinfunction "OUT15_16") (pintype "bidirectional"))
    )
    (net (code "85") (name "OUT2L15") (class "Default")
      (node (ref "LED-TOP") (pin "40") (pinfunction "40_40") (pintype "passive"))
      (node (ref "TLC1") (pin "17") (pinfunction "OUT16_17") (pintype "bidirectional"))
    )
    (net (code "86") (name "OUT3L0") (class "Default")
      (node (ref "LED-BOT") (pin "1") (pinfunction "1_1") (pintype "passive"))
      (node (ref "TLC2") (pin "2") (pinfunction "OUT1_2") (pintype "bidirectional"))
    )
    (net (code "87") (name "OUT3L1") (class "Default")
      (node (ref "LED-BOT") (pin "2") (pinfunction "2_2") (pintype "passive"))
      (node (ref "TLC2") (pin "3") (pinfunction "OUT2_3") (pintype "bidirectional"))
    )
    (net (code "88") (name "OUT3L2") (class "Default")
      (node (ref "LED-BOT") (pin "3") (pinfunction "3_3") (pintype "passive"))
      (node (ref "TLC2") (pin "4") (pinfunction "OUT3_4") (pintype "bidirectional"))
    )
    (net (code "89") (name "OUT3L3") (class "Default")
      (node (ref "LED-BOT") (pin "4") (pinfunction "4_4") (pintype "passive"))
      (node (ref "TLC2") (pin "5") (pinfunction "OUT4_5") (pintype "bidirectional"))
    )
    (net (code "90") (name "OUT3L4") (class "Default")
      (node (ref "LED-BOT") (pin "5") (pinfunction "5_5") (pintype "passive"))
      (node (ref "TLC2") (pin "6") (pinfunction "OUT5_6") (pintype "bidirectional"))
    )
    (net (code "91") (name "OUT3L5") (class "Default")
      (node (ref "LED-BOT") (pin "6") (pinfunction "6_6") (pintype "passive"))
      (node (ref "TLC2") (pin "7") (pinfunction "OUT6_7") (pintype "bidirectional"))
    )
    (net (code "92") (name "OUT3L6") (class "Default")
      (node (ref "LED-BOT") (pin "7") (pinfunction "7_7") (pintype "passive"))
      (node (ref "TLC2") (pin "8") (pinfunction "OUT7_8") (pintype "bidirectional"))
    )
    (net (code "93") (name "OUT3L7") (class "Default")
      (node (ref "LED-BOT") (pin "8") (pinfunction "8_8") (pintype "passive"))
      (node (ref "TLC2") (pin "9") (pinfunction "OUT8_9") (pintype "bidirectional"))
    )
    (net (code "94") (name "OUT3L8") (class "Default")
      (node (ref "LED-BOT") (pin "9") (pinfunction "9_9") (pintype "passive"))
      (node (ref "TLC2") (pin "10") (pinfunction "OUT9_10") (pintype "bidirectional"))
    )
    (net (code "95") (name "OUT3L9") (class "Default")
      (node (ref "LED-BOT") (pin "10") (pinfunction "10_10") (pintype "passive"))
      (node (ref "TLC2") (pin "11") (pinfunction "OUT10_11") (pintype "bidirectional"))
    )
    (net (code "96") (name "OUT3L10") (class "Default")
      (node (ref "LED-BOT") (pin "11") (pinfunction "11_11") (pintype "passive"))
      (node (ref "TLC2") (pin "12") (pinfunction "OUT11_12") (pintype "bidirectional"))
    )
    (net (code "97") (name "OUT3L11") (class "Default")
      (node (ref "LED-BOT") (pin "12") (pinfunction "12_12") (pintype "passive"))
      (node (ref "TLC2") (pin "13") (pinfunction "OUT12_13") (pintype "bidirectional"))
    )
    (net (code "98") (name "OUT3L12") (class "Default")
      (node (ref "LED-BOT") (pin "13") (pinfunction "13_13") (pintype "passive"))
      (node (ref "TLC2") (pin "14") (pinfunction "OUT13_14") (pintype "bidirectional"))
    )
    (net (code "99") (name "OUT3L13") (class "Default")
      (node (ref "LED-BOT") (pin "14") (pinfunction "14_14") (pintype "passive"))
      (node (ref "TLC2") (pin "15") (pinfunction "OUT14_15") (pintype "bidirectional"))
    )
    (net (code "100") (name "OUT3L14") (class "Default")
      (node (ref "LED-BOT") (pin "15") (pinfunction "15_15") (pintype "passive"))
      (node (ref "TLC2") (pin "16") (pinfunction "OUT15_16") (pintype "bidirectional"))
    )
    (net (code "101") (name "OUT3L15") (class "Default")
      (node (ref "LED-BOT") (pin "16") (pinfunction "16_16") (pintype "passive"))
      (node (ref "TLC2") (pin "17") (pinfunction "OUT16_17") (pintype "bidirectional"))
    )
    (net (code "102") (name "OUT4L0") (class "Default")
      (node (ref "LED-BOT") (pin "25") (pinfunction "25_25") (pintype "passive"))
      (node (ref "TLC3") (pin "2") (pinfunction "OUT1_2") (pintype "bidirectional"))
    )
    (net (code "103") (name "OUT4L1") (class "Default")
      (node (ref "LED-BOT") (pin "26") (pinfunction "26_26") (pintype "passive"))
      (node (ref "TLC3") (pin "3") (pinfunction "OUT2_3") (pintype "bidirectional"))
    )
    (net (code "104") (name "OUT4L2") (class "Default")
      (node (ref "LED-BOT") (pin "27") (pinfunction "27_27") (pintype "passive"))
      (node (ref "TLC3") (pin "4") (pinfunction "OUT3_4") (pintype "bidirectional"))
    )
    (net (code "105") (name "OUT4L3") (class "Default")
      (node (ref "LED-BOT") (pin "28") (pinfunction "28_28") (pintype "passive"))
      (node (ref "TLC3") (pin "5") (pinfunction "OUT4_5") (pintype "bidirectional"))
    )
    (net (code "106") (name "OUT4L4") (class "Default")
      (node (ref "LED-BOT") (pin "29") (pinfunction "29_29") (pintype "passive"))
      (node (ref "TLC3") (pin "6") (pinfunction "OUT5_6") (pintype "bidirectional"))
    )
    (net (code "107") (name "OUT4L5") (class "Default")
      (node (ref "LED-BOT") (pin "30") (pinfunction "30_30") (pintype "passive"))
      (node (ref "TLC3") (pin "7") (pinfunction "OUT6_7") (pintype "bidirectional"))
    )
    (net (code "108") (name "OUT4L6") (class "Default")
      (node (ref "LED-BOT") (pin "31") (pinfunction "31_31") (pintype "passive"))
      (node (ref "TLC3") (pin "8") (pinfunction "OUT7_8") (pintype "bidirectional"))
    )
    (net (code "109") (name "OUT4L7") (class "Default")
      (node (ref "LED-BOT") (pin "32") (pinfunction "32_32") (pintype "passive"))
      (node (ref "TLC3") (pin "9") (pinfunction "OUT8_9") (pintype "bidirectional"))
    )
    (net (code "110") (name "OUT4L8") (class "Default")
      (node (ref "LED-BOT") (pin "33") (pinfunction "33_33") (pintype "passive"))
      (node (ref "TLC3") (pin "10") (pinfunction "OUT9_10") (pintype "bidirectional"))
    )
    (net (code "111") (name "OUT4L9") (class "Default")
      (node (ref "LED-BOT") (pin "34") (pinfunction "34_34") (pintype "passive"))
      (node (ref "TLC3") (pin "11") (pinfunction "OUT10_11") (pintype "bidirectional"))
    )
    (net (code "112") (name "OUT4L10") (class "Default")
      (node (ref "LED-BOT") (pin "35") (pinfunction "35_35") (pintype "passive"))
      (node (ref "TLC3") (pin "12") (pinfunction "OUT11_12") (pintype "bidirectional"))
    )
    (net (code "113") (name "OUT4L11") (class "Default")
      (node (ref "LED-BOT") (pin "36") (pinfunction "36_36") (pintype "passive"))
      (node (ref "TLC3") (pin "13") (pinfunction "OUT12_13") (pintype "bidirectional"))
    )
    (net (code "114") (name "OUT4L12") (class "Default")
      (node (ref "LED-BOT") (pin "37") (pinfunction "37_37") (pintype "passive"))
      (node (ref "TLC3") (pin "14") (pinfunction "OUT13_14") (pintype "bidirectional"))
    )
    (net (code "115") (name "OUT4L13") (class "Default")
      (node (ref "LED-BOT") (pin "38") (pinfunction "38_38") (pintype "passive"))
      (node (ref "TLC3") (pin "15") (pinfunction "OUT14_15") (pintype "bidirectional"))
    )
    (net (code "116") (name "OUT4L14") (class "Default")
      (node (ref "LED-BOT") (pin "39") (pinfunction "39_39") (pintype "passive"))
      (node (ref "TLC3") (pin "16") (pinfunction "OUT15_16") (pintype "bidirectional"))
    )
    (net (code "117") (name "OUT4L15") (class "Default")
      (node (ref "LED-BOT") (pin "40") (pinfunction "40_40") (pintype "passive"))
      (node (ref "TLC3") (pin "17") (pinfunction "OUT16_17") (pintype "bidirectional"))
    )
    (net (code "118") (name "PORTB0") (class "Default")
      (node (ref "IC1") (pin "40") (pinfunction "(XCK0/T0/PCINT8)PB0_40") (pintype "bidirectional"))
      (node (ref "PB0") (pin "1") (pinfunction "1_1") (pintype "passive"))
    )
    (net (code "119") (name "PORTB1") (class "Default")
      (node (ref "IC1") (pin "41") (pinfunction "(CLKO/T1/PCINT9)PB1_41") (pintype "bidirectional"))
      (node (ref "PB1") (pin "1") (pinfunction "1_1") (pintype "passive"))
    )
    (net (code "120") (name "PORTB2") (class "Default")
      (node (ref "IC1") (pin "42") (pinfunction "(INT2/AIN0/PCINT10)PB2_42") (pintype "bidirectional"))
      (node (ref "PB2") (pin "1") (pinfunction "1_1") (pintype "passive"))
    )
    (net (code "121") (name "PORTB3") (class "Default")
      (node (ref "IC1") (pin "43") (pinfunction "(OC0A/AIN1/PCINT11)PB3_43") (pintype "bidirectional"))
      (node (ref "PB3") (pin "1") (pinfunction "1_1") (pintype "passive"))
    )
    (net (code "122") (name "RXD") (class "Default")
      (node (ref "IC1") (pin "10") (pinfunction "(TXD0/PCINT25)PD1_10") (pintype "bidirectional"))
      (node (ref "R13") (pin "2") (pinfunction "2_2") (pintype "passive"))
    )
    (net (code "123") (name "RXD1") (class "Default")
      (node (ref "IC1") (pin "11") (pinfunction "(RXD1/INT0/PCINT26)PD2_11") (pintype "bidirectional"))
      (node (ref "RXD") (pin "1") (pinfunction "1_1") (pintype "passive"))
    )
    (net (code "124") (name "SCK") (class "Default")
      (node (ref "IC1") (pin "3") (pinfunction "(SCK/PCINT15)PB7_3") (pintype "bidirectional"))
      (node (ref "JP3") (pin "3") (pinfunction "3_3") (pintype "passive"))
    )
    (net (code "125") (name "SCKD") (class "Default")
      (node (ref "IC1") (pin "26") (pinfunction "(TOSC2/PCINT23)PC7_26") (pintype "bidirectional"))
      (node (ref "TLC0") (pin "24") (pinfunction "SCLK_24") (pintype "bidirectional"))
      (node (ref "TLC1") (pin "24") (pinfunction "SCLK_24") (pintype "bidirectional"))
      (node (ref "TLC2") (pin "24") (pinfunction "SCLK_24") (pintype "bidirectional"))
      (node (ref "TLC3") (pin "24") (pinfunction "SCLK_24") (pintype "bidirectional"))
    )
    (net (code "126") (name "SCL") (class "Default")
      (node (ref "IC1") (pin "19") (pinfunction "(SCL/PCINT16)PC0_19") (pintype "bidirectional"))
      (node (ref "SCL") (pin "1") (pinfunction "1_1") (pintype "passive"))
    )
    (net (code "127") (name "SDA") (class "Default")
      (node (ref "IC1") (pin "20") (pinfunction "(SDA/PCINT17)PC1_20") (pintype "bidirectional"))
      (node (ref "SDA") (pin "1") (pinfunction "1_1") (pintype "passive"))
    )
    (net (code "128") (name "SDAD0") (class "Default")
      (node (ref "IC1") (pin "21") (pinfunction "(TCK/PCINT18)PC2_21") (pintype "bidirectional"))
      (node (ref "TLC0") (pin "23") (pinfunction "SIN_23") (pintype "bidirectional"))
    )
    (net (code "129") (name "SDAD1") (class "Default")
      (node (ref "IC1") (pin "23") (pinfunction "(TDO/PCINT20)PC4_23") (pintype "bidirectional"))
      (node (ref "TLC1") (pin "23") (pinfunction "SIN_23") (pintype "bidirectional"))
    )
    (net (code "130") (name "SDAD2") (class "Default")
      (node (ref "IC1") (pin "24") (pinfunction "(TDI/PCINT21)PC5_24") (pintype "bidirectional"))
      (node (ref "TLC2") (pin "23") (pinfunction "SIN_23") (pintype "bidirectional"))
    )
    (net (code "131") (name "SDAD3") (class "Default")
      (node (ref "IC1") (pin "22") (pinfunction "(TMS/PCINT19)PC3_22") (pintype "bidirectional"))
      (node (ref "TLC3") (pin "23") (pinfunction "SIN_23") (pintype "bidirectional"))
    )
    (net (code "132") (name "TXD") (class "Default")
      (node (ref "IC1") (pin "9") (pinfunction "(RXD0/PCINT24)PD0_9") (pintype "bidirectional"))
      (node (ref "R20") (pin "1") (pinfunction "1_1") (pintype "passive"))
      (node (ref "T4") (pin "3") (pinfunction "C_3") (pintype "passive"))
    )
    (net (code "133") (name "TXD1") (class "Default")
      (node (ref "IC1") (pin "12") (pinfunction "(TXD1/INT1/PCINT27)PD3_12") (pintype "bidirectional"))
      (node (ref "TXD") (pin "1") (pinfunction "1_1") (pintype "passive"))
    )
    (net (code "134") (name "V+") (class "Default")
      (node (ref "C13") (pin "+") (pinfunction "+_+") (pintype "passive"))
      (node (ref "C14") (pin "2") (pinfunction "2_2") (pintype "passive"))
      (node (ref "C15") (pin "1") (pinfunction "1_1") (pintype "passive"))
      (node (ref "IC3") (pin "3") (pinfunction "IN_3") (pintype "input"))
      (node (ref "IRF0") (pin "1") (pinfunction "S_1") (pintype "bidirectional"))
      (node (ref "IRF0") (pin "3") (pinfunction "S_3") (pintype "bidirectional"))
      (node (ref "IRF1") (pin "1") (pinfunction "S_1") (pintype "bidirectional"))
      (node (ref "IRF1") (pin "3") (pinfunction "S_3") (pintype "bidirectional"))
      (node (ref "IRF2") (pin "1") (pinfunction "S_1") (pintype "bidirectional"))
      (node (ref "IRF2") (pin "3") (pinfunction "S_3") (pintype "bidirectional"))
      (node (ref "IRF3") (pin "1") (pinfunction "S_1") (pintype "bidirectional"))
      (node (ref "IRF3") (pin "3") (pinfunction "S_3") (pintype "bidirectional"))
      (node (ref "VCC") (pin "1") (pinfunction "P_1") (pintype "passive"))
    )
    (net (code "135") (name "VCC") (class "Default")
      (node (ref "C1") (pin "1") (pinfunction "1_1") (pintype "passive"))
      (node (ref "C10") (pin "2") (pinfunction "2_2") (pintype "passive"))
      (node (ref "C11") (pin "2") (pinfunction "2_2") (pintype "passive"))
      (node (ref "C12") (pin "2") (pinfunction "2_2") (pintype "passive"))
      (node (ref "C16") (pin "1") (pinfunction "1_1") (pintype "passive"))
      (node (ref "C5") (pin "2") (pinfunction "2_2") (pintype "passive"))
      (node (ref "C6") (pin "2") (pinfunction "2_2") (pintype "passive"))
      (node (ref "C7") (pin "2") (pinfunction "2_2") (pintype "passive"))
      (node (ref "C8") (pin "2") (pinfunction "2_2") (pintype "passive"))
      (node (ref "C9") (pin "2") (pinfunction "2_2") (pintype "passive"))
      (node (ref "IC1") (pin "17") (pinfunction "VCC_17") (pintype "power_in"))
      (node (ref "IC1") (pin "27") (pinfunction "AVCC_27") (pintype "power_in"))
      (node (ref "IC1") (pin "29") (pinfunction "AREF_29") (pintype "power_in"))
      (node (ref "IC1") (pin "38") (pinfunction "VCC_38") (pintype "power_in"))
      (node (ref "IC1") (pin "5") (pinfunction "VCC_5") (pintype "power_in"))
      (node (ref "IC3") (pin "4") (pinfunction "OUT_4") (pintype "passive"))
      (node (ref "IC4") (pin "3") (pinfunction "IN_3") (pintype "input"))
      (node (ref "JP3") (pin "2") (pinfunction "2_2") (pintype "passive"))
      (node (ref "R12") (pin "2") (pinfunction "2_2") (pintype "passive"))
      (node (ref "R19") (pin "2") (pinfunction "2_2") (pintype "passive"))
      (node (ref "R20") (pin "2") (pinfunction "2_2") (pintype "passive"))
      (node (ref "R29") (pin "2") (pinfunction "2_2") (pintype "passive"))
      (node (ref "TLC0") (pin "21") (pinfunction "VCC_21") (pintype "bidirectional"))
      (node (ref "TLC1") (pin "21") (pinfunction "VCC_21") (pintype "bidirectional"))
      (node (ref "TLC2") (pin "21") (pinfunction "VCC_21") (pintype "bidirectional"))
      (node (ref "TLC3") (pin "21") (pinfunction "VCC_21") (pintype "bidirectional"))
    )
    (net (code "136") (name "unconnected-(IC1-(OC1A{slash}PCINT29)PD5-Pad14)") (class "Default")
      (node (ref "IC1") (pin "14") (pinfunction "(OC1A/PCINT29)PD5_14") (pintype "bidirectional"))
    )
    (net (code "137") (name "unconnected-(IC1-(OC2B{slash}ICP{slash}PCINT30)PD6-Pad15)") (class "Default")
      (node (ref "IC1") (pin "15") (pinfunction "(OC2B/ICP/PCINT30)PD6_15") (pintype "bidirectional"))
    )
    (net (code "138") (name "unconnected-(IC1-(XCK1{slash}OC1B{slash}PCINT28)PD4-Pad13)") (class "Default")
      (node (ref "IC1") (pin "13") (pinfunction "(XCK1/OC1B/PCINT28)PD4_13") (pintype "bidirectional"))
    )
    (net (code "139") (name "unconnected-(IC2-CTS-PadP$30)") (class "Default")
      (node (ref "IC2") (pin "P$30") (pinfunction "CTS_P$30") (pintype "bidirectional"))
    )
    (net (code "140") (name "unconnected-(IC2-PIO4-PadP$9)") (class "Default")
      (node (ref "IC2") (pin "P$9") (pinfunction "PIO4_P$9") (pintype "bidirectional"))
    )
    (net (code "141") (name "unconnected-(IC2-PIO6-PadP$12)") (class "Default")
      (node (ref "IC2") (pin "P$12") (pinfunction "PIO6_P$12") (pintype "bidirectional"))
    )
    (net (code "142") (name "unconnected-(IC2-RTS-PadP$28)") (class "Default")
      (node (ref "IC2") (pin "P$28") (pinfunction "RTS_P$28") (pintype "bidirectional"))
    )
    (net (code "143") (name "unconnected-(LED-BOT-Pad17)") (class "Default")
      (node (ref "LED-BOT") (pin "17") (pinfunction "17_17") (pintype "passive"))
    )
    (net (code "144") (name "unconnected-(LED-BOT-Pad18)") (class "Default")
      (node (ref "LED-BOT") (pin "18") (pinfunction "18_18") (pintype "passive"))
    )
    (net (code "145") (name "unconnected-(LED-BOT-Pad23)") (class "Default")
      (node (ref "LED-BOT") (pin "23") (pinfunction "23_23") (pintype "passive"))
    )
    (net (code "146") (name "unconnected-(LED-BOT-Pad24)") (class "Default")
      (node (ref "LED-BOT") (pin "24") (pinfunction "24_24") (pintype "passive"))
    )
    (net (code "147") (name "unconnected-(LED-TOP-Pad17)") (class "Default")
      (node (ref "LED-TOP") (pin "17") (pinfunction "17_17") (pintype "passive"))
    )
    (net (code "148") (name "unconnected-(LED-TOP-Pad18)") (class "Default")
      (node (ref "LED-TOP") (pin "18") (pinfunction "18_18") (pintype "passive"))
    )
    (net (code "149") (name "unconnected-(LED-TOP-Pad23)") (class "Default")
      (node (ref "LED-TOP") (pin "23") (pinfunction "23_23") (pintype "passive"))
    )
    (net (code "150") (name "unconnected-(LED-TOP-Pad24)") (class "Default")
      (node (ref "LED-TOP") (pin "24") (pinfunction "24_24") (pintype "passive"))
    )
    (net (code "151") (name "unconnected-(TLC0-SOUT-Pad19)") (class "Default")
      (node (ref "TLC0") (pin "19") (pinfunction "SOUT_19") (pintype "bidirectional"))
    )
    (net (code "152") (name "unconnected-(TLC1-SOUT-Pad19)") (class "Default")
      (node (ref "TLC1") (pin "19") (pinfunction "SOUT_19") (pintype "bidirectional"))
    )
    (net (code "153") (name "unconnected-(TLC2-SOUT-Pad19)") (class "Default")
      (node (ref "TLC2") (pin "19") (pinfunction "SOUT_19") (pintype "bidirectional"))
    )
    (net (code "154") (name "unconnected-(TLC3-SOUT-Pad19)") (class "Default")
      (node (ref "TLC3") (pin "19") (pinfunction "SOUT_19") (pintype "bidirectional"))
    )
  )
)
